# 01_Raspberry_Hat_4_Schematic.net
KiCad netlist of a schematic drawn in EAGLE
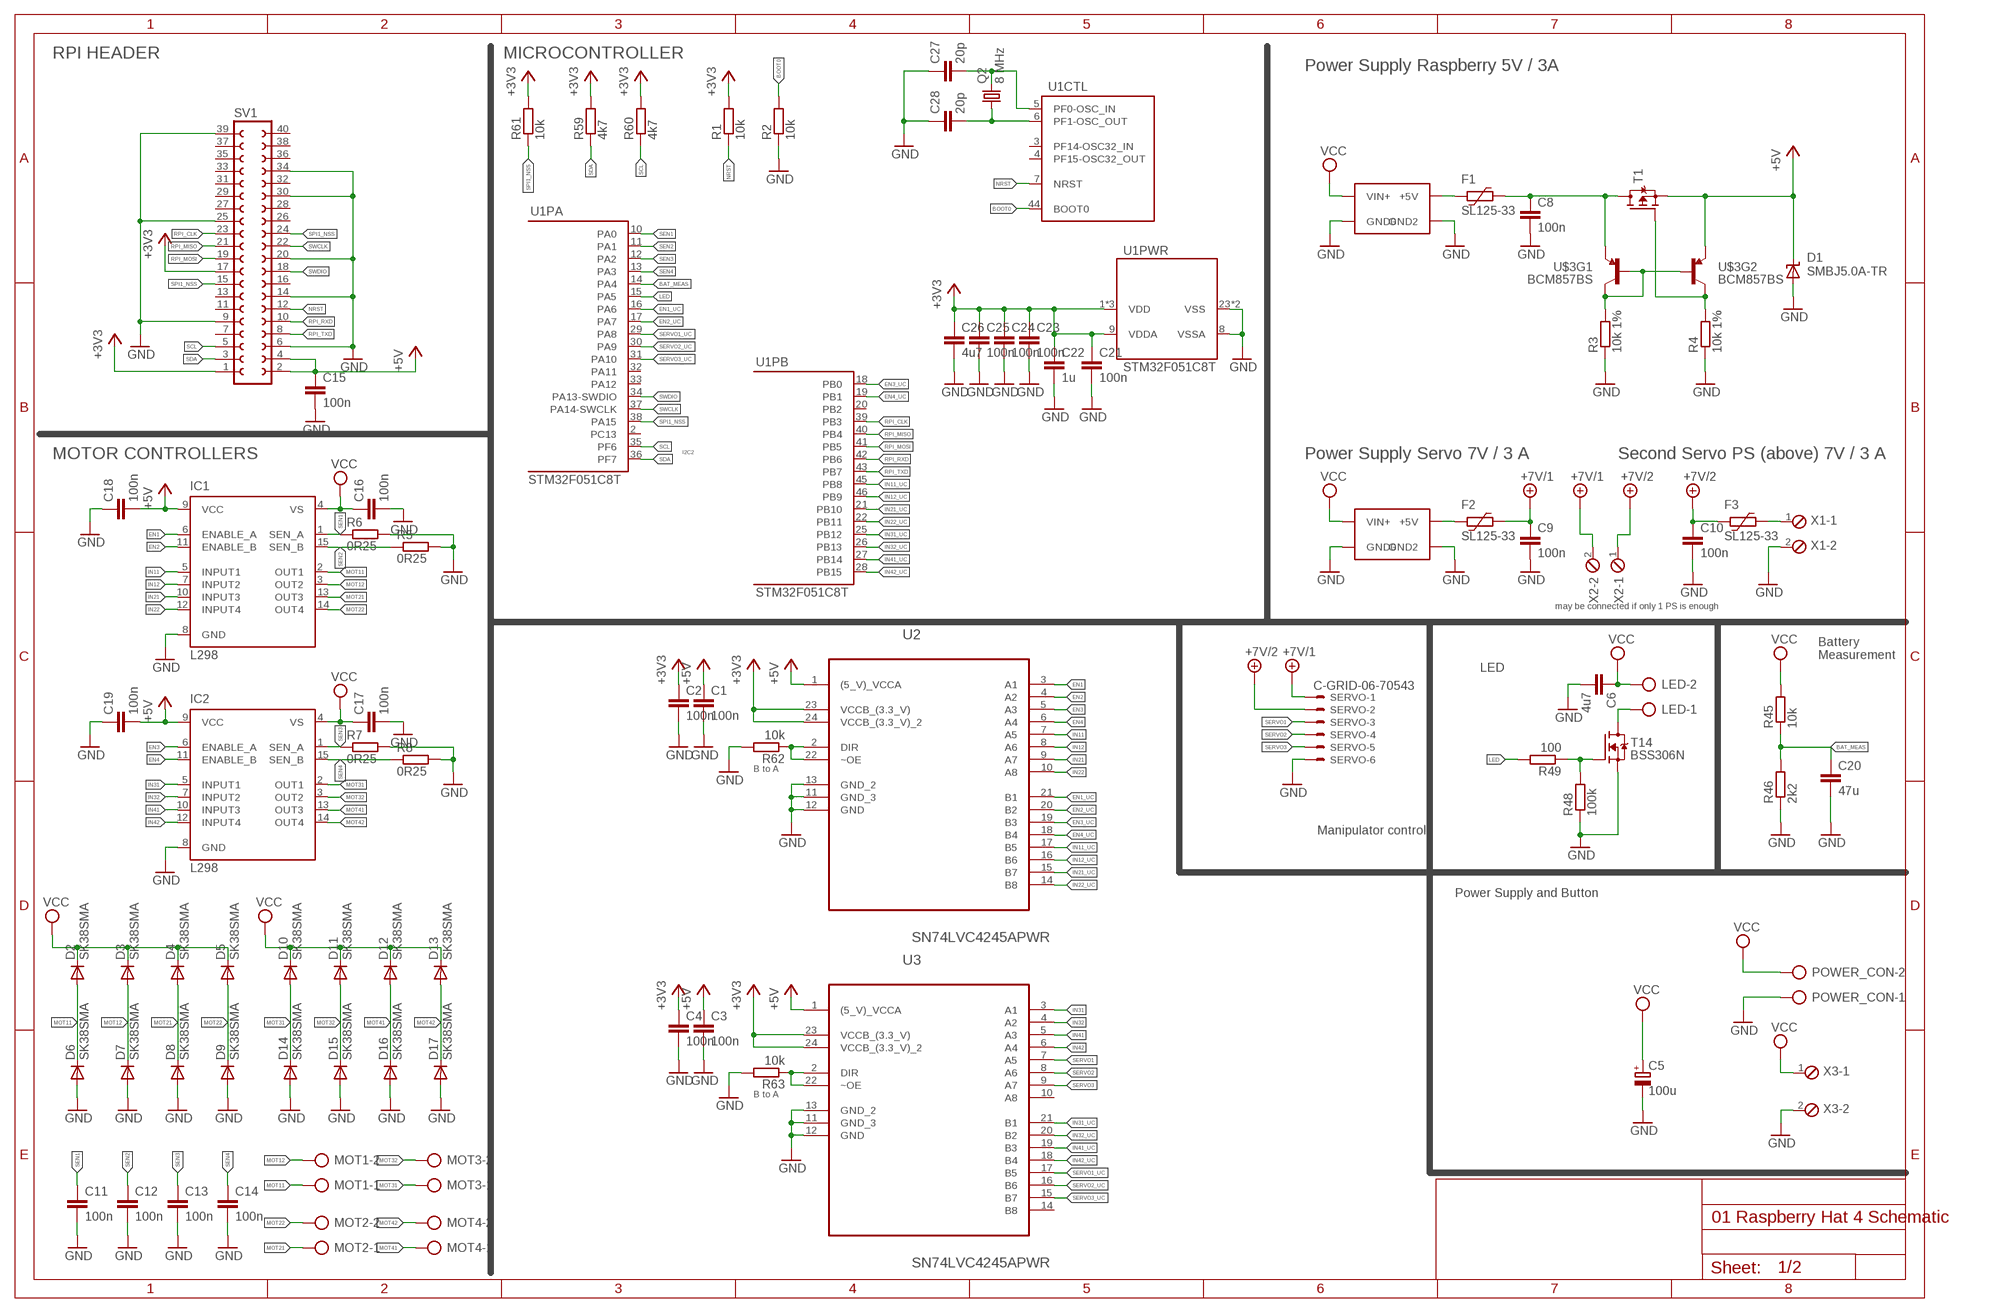
[diagram p0: schematic, sheet 1]
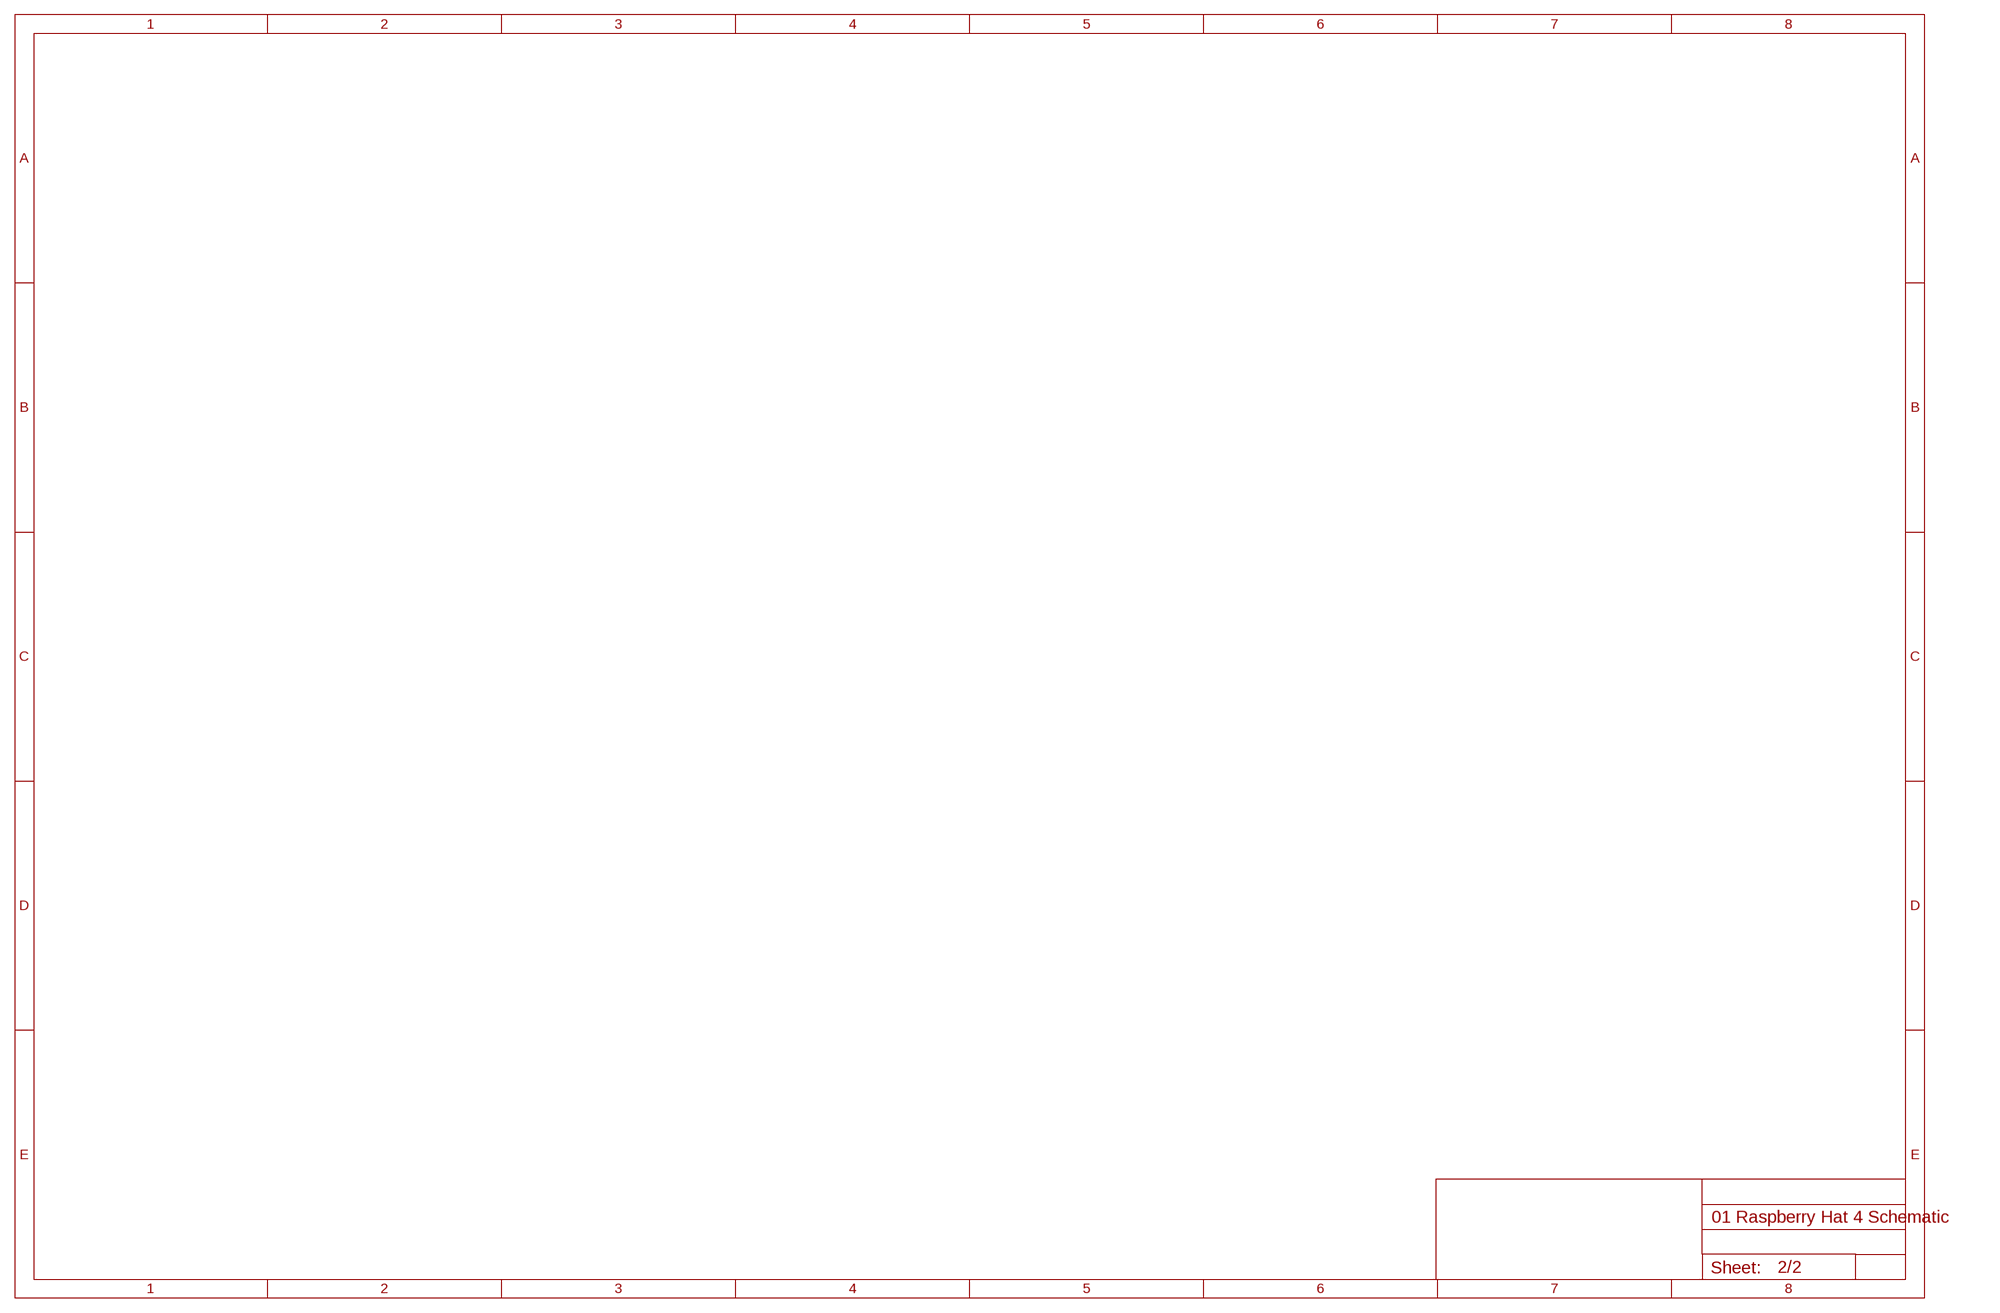
[diagram p1: schematic, sheet 2]

(export (version "E")
  (design (tool "Eeschema 10.0.6"))
  (components
    (comp (ref "C1")
      (value "100n")
      (footprint "eagle-import:C0805")
      (libsource (lib "eagle-import") (part "C-EUC0805"))
    )
    (comp (ref "C2")
      (value "100n")
      (footprint "eagle-import:C0805")
      (libsource (lib "eagle-import") (part "C-EUC0805"))
    )
    (comp (ref "C3")
      (value "100n")
      (footprint "eagle-import:C0805")
      (libsource (lib "eagle-import") (part "C-EUC0805"))
    )
    (comp (ref "C4")
      (value "100n")
      (footprint "eagle-import:C0805")
      (libsource (lib "eagle-import") (part "C-EUC0805"))
    )
    (comp (ref "C5")
      (value "100u")
      (footprint "eagle-import:153CLV-0807")
      (libsource (lib "eagle-import") (part "CPOL-EU153CLV-0807"))
    )
    (comp (ref "C6")
      (value "4u7")
      (footprint "eagle-import:C0805")
      (libsource (lib "eagle-import") (part "C-EUC0805"))
    )
    (comp (ref "C8")
      (value "100n")
      (footprint "eagle-import:C0805")
      (libsource (lib "eagle-import") (part "C-EUC0805"))
    )
    (comp (ref "C9")
      (value "100n")
      (footprint "eagle-import:C0805")
      (libsource (lib "eagle-import") (part "C-EUC0805"))
    )
    (comp (ref "C10")
      (value "100n")
      (footprint "eagle-import:C0805")
      (libsource (lib "eagle-import") (part "C-EUC0805"))
    )
    (comp (ref "C11")
      (value "100n")
      (footprint "eagle-import:C0805")
      (libsource (lib "eagle-import") (part "C-EUC0805"))
    )
    (comp (ref "C12")
      (value "100n")
      (footprint "eagle-import:C0805")
      (libsource (lib "eagle-import") (part "C-EUC0805"))
    )
    (comp (ref "C13")
      (value "100n")
      (footprint "eagle-import:C0805")
      (libsource (lib "eagle-import") (part "C-EUC0805"))
    )
    (comp (ref "C14")
      (value "100n")
      (footprint "eagle-import:C0805")
      (libsource (lib "eagle-import") (part "C-EUC0805"))
    )
    (comp (ref "C15")
      (value "100n")
      (footprint "eagle-import:C0805")
      (libsource (lib "eagle-import") (part "C-EUC0805"))
    )
    (comp (ref "C16")
      (value "100n")
      (footprint "eagle-import:C0805")
      (libsource (lib "eagle-import") (part "C-EUC0805"))
    )
    (comp (ref "C17")
      (value "100n")
      (footprint "eagle-import:C0805")
      (libsource (lib "eagle-import") (part "C-EUC0805"))
    )
    (comp (ref "C18")
      (value "100n")
      (footprint "eagle-import:C0805")
      (libsource (lib "eagle-import") (part "C-EUC0805"))
    )
    (comp (ref "C19")
      (value "100n")
      (footprint "eagle-import:C0805")
      (libsource (lib "eagle-import") (part "C-EUC0805"))
    )
    (comp (ref "C20")
      (value "47u")
      (footprint "eagle-import:C0805")
      (libsource (lib "eagle-import") (part "C-EUC0805"))
    )
    (comp (ref "C21")
      (value "100n")
      (footprint "eagle-import:C0805")
      (libsource (lib "eagle-import") (part "C-EUC0805"))
    )
    (comp (ref "C22")
      (value "1u")
      (footprint "eagle-import:C0805")
      (libsource (lib "eagle-import") (part "C-EUC0805"))
    )
    (comp (ref "C23")
      (value "100n")
      (footprint "eagle-import:C0805")
      (libsource (lib "eagle-import") (part "C-EUC0805"))
    )
    (comp (ref "C24")
      (value "100n")
      (footprint "eagle-import:C0805")
      (libsource (lib "eagle-import") (part "C-EUC0805"))
    )
    (comp (ref "C25")
      (value "100n")
      (footprint "eagle-import:C0805")
      (libsource (lib "eagle-import") (part "C-EUC0805"))
    )
    (comp (ref "C26")
      (value "4u7")
      (footprint "eagle-import:C0805")
      (libsource (lib "eagle-import") (part "C-EUC0805"))
    )
    (comp (ref "C27")
      (value "20p")
      (footprint "eagle-import:C0805")
      (libsource (lib "eagle-import") (part "C-EUC0805"))
    )
    (comp (ref "C28")
      (value "20p")
      (footprint "eagle-import:C0805")
      (libsource (lib "eagle-import") (part "C-EUC0805"))
    )
    (comp (ref "D1")
      (value "SMBJ5.0A-TR")
      (footprint "eagle-import:SMBJ")
      (libsource (lib "eagle-import") (part "SUPPRESSOR-SMBJ"))
    )
    (comp (ref "D2")
      (value "SK38SMA")
      (footprint "eagle-import:DO214AC")
      (libsource (lib "eagle-import") (part "DIODE-DO214AC"))
    )
    (comp (ref "D3")
      (value "SK38SMA")
      (footprint "eagle-import:DO214AC")
      (libsource (lib "eagle-import") (part "DIODE-DO214AC"))
    )
    (comp (ref "D4")
      (value "SK38SMA")
      (footprint "eagle-import:DO214AC")
      (libsource (lib "eagle-import") (part "DIODE-DO214AC"))
    )
    (comp (ref "D5")
      (value "SK38SMA")
      (footprint "eagle-import:DO214AC")
      (libsource (lib "eagle-import") (part "DIODE-DO214AC"))
    )
    (comp (ref "D6")
      (value "SK38SMA")
      (footprint "eagle-import:DO214AC")
      (libsource (lib "eagle-import") (part "DIODE-DO214AC"))
    )
    (comp (ref "D7")
      (value "SK38SMA")
      (footprint "eagle-import:DO214AC")
      (libsource (lib "eagle-import") (part "DIODE-DO214AC"))
    )
    (comp (ref "D8")
      (value "SK38SMA")
      (footprint "eagle-import:DO214AC")
      (libsource (lib "eagle-import") (part "DIODE-DO214AC"))
    )
    (comp (ref "D9")
      (value "SK38SMA")
      (footprint "eagle-import:DO214AC")
      (libsource (lib "eagle-import") (part "DIODE-DO214AC"))
    )
    (comp (ref "D10")
      (value "SK38SMA")
      (footprint "eagle-import:DO214AC")
      (libsource (lib "eagle-import") (part "DIODE-DO214AC"))
    )
    (comp (ref "D11")
      (value "SK38SMA")
      (footprint "eagle-import:DO214AC")
      (libsource (lib "eagle-import") (part "DIODE-DO214AC"))
    )
    (comp (ref "D12")
      (value "SK38SMA")
      (footprint "eagle-import:DO214AC")
      (libsource (lib "eagle-import") (part "DIODE-DO214AC"))
    )
    (comp (ref "D13")
      (value "SK38SMA")
      (footprint "eagle-import:DO214AC")
      (libsource (lib "eagle-import") (part "DIODE-DO214AC"))
    )
    (comp (ref "D14")
      (value "SK38SMA")
      (footprint "eagle-import:DO214AC")
      (libsource (lib "eagle-import") (part "DIODE-DO214AC"))
    )
    (comp (ref "D15")
      (value "SK38SMA")
      (footprint "eagle-import:DO214AC")
      (libsource (lib "eagle-import") (part "DIODE-DO214AC"))
    )
    (comp (ref "D16")
      (value "SK38SMA")
      (footprint "eagle-import:DO214AC")
      (libsource (lib "eagle-import") (part "DIODE-DO214AC"))
    )
    (comp (ref "D17")
      (value "SK38SMA")
      (footprint "eagle-import:DO214AC")
      (libsource (lib "eagle-import") (part "DIODE-DO214AC"))
    )
    (comp (ref "F1")
      (value "SL125-33")
      (footprint "eagle-import:2920L")
      (fields (field (name "MF") "Littelfuse") (field (name "MPN") "2920L050"))
      (libsource (lib "eagle-import") (part "?2920L050"))
    )
    (comp (ref "F2")
      (value "SL125-33")
      (footprint "eagle-import:2920L")
      (fields (field (name "MF") "Littelfuse") (field (name "MPN") "2920L050"))
      (libsource (lib "eagle-import") (part "?2920L050"))
    )
    (comp (ref "F3")
      (value "SL125-33")
      (footprint "eagle-import:2920L")
      (fields (field (name "MF") "Littelfuse") (field (name "MPN") "2920L050"))
      (libsource (lib "eagle-import") (part "?2920L050"))
    )
    (comp (ref "IC1")
      (value "L298")
      (footprint "eagle-import:MULTIWATT-15")
      (fields (field (name "MPN") "L298N"))
      (libsource (lib "eagle-import") (part "L298"))
    )
    (comp (ref "IC2")
      (value "L298")
      (footprint "eagle-import:MULTIWATT-15")
      (fields (field (name "MPN") "L298N"))
      (libsource (lib "eagle-import") (part "L298"))
    )
    (comp (ref "LED")
      (value "AK500/2")
      (footprint "eagle-import:AK500_2")
      (libsource (lib "eagle-import") (part "AK500/2"))
    )
    (comp (ref "MOT1")
      (value "AK500/2")
      (footprint "eagle-import:AK500_2")
      (libsource (lib "eagle-import") (part "AK500/2"))
    )
    (comp (ref "MOT2")
      (value "AK500/2")
      (footprint "eagle-import:AK500_2")
      (libsource (lib "eagle-import") (part "AK500/2"))
    )
    (comp (ref "MOT3")
      (value "AK500/2")
      (footprint "eagle-import:AK500_2")
      (libsource (lib "eagle-import") (part "AK500/2"))
    )
    (comp (ref "MOT4")
      (value "AK500/2")
      (footprint "eagle-import:AK500_2")
      (libsource (lib "eagle-import") (part "AK500/2"))
    )
    (comp (ref "POWER_CON")
      (value "AK500/2")
      (footprint "eagle-import:AK500_2")
      (libsource (lib "eagle-import") (part "AK500/2"))
    )
    (comp (ref "Q2")
      (value "8 MHz")
      (footprint "eagle-import:HC49UP")
      (libsource (lib "eagle-import") (part "CRYSTALHC49UP"))
    )
    (comp (ref "R1")
      (value "10k")
      (footprint "eagle-import:M0805")
      (libsource (lib "eagle-import") (part "resistor_R-EU_M0805"))
    )
    (comp (ref "R2")
      (value "10k")
      (footprint "eagle-import:M0805")
      (libsource (lib "eagle-import") (part "resistor_R-EU_M0805"))
    )
    (comp (ref "R3")
      (value "10k 1%")
      (footprint "eagle-import:M0805")
      (libsource (lib "eagle-import") (part "resistor_R-EU_M0805"))
    )
    (comp (ref "R4")
      (value "10k 1%")
      (footprint "eagle-import:M0805")
      (libsource (lib "eagle-import") (part "resistor_R-EU_M0805"))
    )
    (comp (ref "R5")
      (value "0R25")
      (footprint "eagle-import:R2512")
      (libsource (lib "eagle-import") (part "R-EU_R2512"))
    )
    (comp (ref "R6")
      (value "0R25")
      (footprint "eagle-import:R2512")
      (libsource (lib "eagle-import") (part "R-EU_R2512"))
    )
    (comp (ref "R7")
      (value "0R25")
      (footprint "eagle-import:R2512")
      (libsource (lib "eagle-import") (part "R-EU_R2512"))
    )
    (comp (ref "R8")
      (value "0R25")
      (footprint "eagle-import:R2512")
      (libsource (lib "eagle-import") (part "R-EU_R2512"))
    )
    (comp (ref "R45")
      (value "10k")
      (footprint "eagle-import:M0805")
      (libsource (lib "eagle-import") (part "resistor_R-EU_M0805"))
    )
    (comp (ref "R46")
      (value "2k2")
      (footprint "eagle-import:M0805")
      (libsource (lib "eagle-import") (part "resistor_R-EU_M0805"))
    )
    (comp (ref "R48")
      (value "100k")
      (footprint "eagle-import:M0805")
      (libsource (lib "eagle-import") (part "resistor_R-EU_M0805"))
    )
    (comp (ref "R49")
      (value "100")
      (footprint "eagle-import:M0805")
      (libsource (lib "eagle-import") (part "resistor_R-EU_M0805"))
    )
    (comp (ref "R59")
      (value "4k7")
      (footprint "eagle-import:M0805")
      (libsource (lib "eagle-import") (part "resistor_R-EU_M0805"))
    )
    (comp (ref "R60")
      (value "4k7")
      (footprint "eagle-import:M0805")
      (libsource (lib "eagle-import") (part "resistor_R-EU_M0805"))
    )
    (comp (ref "R61")
      (value "10k")
      (footprint "eagle-import:M0805")
      (libsource (lib "eagle-import") (part "resistor_R-EU_M0805"))
    )
    (comp (ref "R62")
      (value "10k")
      (footprint "eagle-import:M0805")
      (libsource (lib "eagle-import") (part "resistor_R-EU_M0805"))
    )
    (comp (ref "R63")
      (value "10k")
      (footprint "eagle-import:M0805")
      (libsource (lib "eagle-import") (part "resistor_R-EU_M0805"))
    )
    (comp (ref "SERVO")
      (value "C-GRID-06-70543")
      (footprint "eagle-import:70543-06")
      (fields
        (field (name "LINK") "http://www.tme.eu/pl/details/ncdw-06/zlacza-sygnalowe-raster-254mm/ninigi/")
      )
      (libsource (lib "eagle-import") (part "C-GRID-06-70543"))
    )
    (comp (ref "SV1")
      (value "FE20-2")
      (footprint "eagle-import:FE20-2")
      (libsource (lib "eagle-import") (part "FE20-2"))
    )
    (comp (ref "T1")
      (value "MOSFET-P-SOT23")
      (footprint "eagle-import:SOT23")
      (libsource (lib "eagle-import") (part "MOSFET-P-SOT23"))
    )
    (comp (ref "T14")
      (value "BSS306N")
      (footprint "eagle-import:SOT23")
      (libsource (lib "eagle-import") (part "MOSFET-N-SOT23"))
    )
    (comp (ref "U$2")
      (value "LM2596_CONVERTER")
      (footprint "eagle-import:LM2596_CONVERTER")
      (libsource (lib "eagle-import") (part "LM2596_CONVERTER"))
    )
    (comp (ref "U$3")
      (value "BCM857BS")
      (footprint "eagle-import:SOT363")
      (fields (field (name "LINK") "http://www.tme.eu/pl/details/bcm857bs/tranzystory-pnp-smd/nxp/"))
      (libsource (lib "eagle-import") (part "BCM857BS"))
    )
    (comp (ref "U$4")
      (value "LM2596_CONVERTER")
      (footprint "eagle-import:LM2596_CONVERTER")
      (libsource (lib "eagle-import") (part "LM2596_CONVERTER"))
    )
    (comp (ref "U1")
      (value "STM32F051C8T")
      (footprint "eagle-import:LQFP48")
      (libsource (lib "eagle-import") (part "STM32F051CT8"))
    )
    (comp (ref "U2")
      (value "SN74LVC4245APWR")
      (footprint "eagle-import:SOP65P640X120-24N")
      (libsource (lib "eagle-import") (part "SN74LVC4245APWR"))
    )
    (comp (ref "U3")
      (value "SN74LVC4245APWR")
      (footprint "eagle-import:SOP65P640X120-24N")
      (libsource (lib "eagle-import") (part "SN74LVC4245APWR"))
    )
    (comp (ref "X1")
      (value "MPT2")
      (footprint "eagle-import:2POL254")
      (libsource (lib "eagle-import") (part "MPT2"))
    )
    (comp (ref "X2")
      (value "MPT2")
      (footprint "eagle-import:2POL254")
      (libsource (lib "eagle-import") (part "MPT2"))
    )
    (comp (ref "X3")
      (value "MPT2")
      (footprint "eagle-import:2POL254")
      (libsource (lib "eagle-import") (part "MPT2"))
    )
  )
  (nets
    (net (code "1") (name "+3V3") (class "Default")
      (node (ref "C2") (pin "1") (pinfunction "1_1") (pintype "passive"))
      (node (ref "C21") (pin "1") (pinfunction "1_1") (pintype "passive"))
      (node (ref "C22") (pin "1") (pinfunction "1_1") (pintype "passive"))
      (node (ref "C23") (pin "1") (pinfunction "1_1") (pintype "passive"))
      (node (ref "C24") (pin "1") (pinfunction "1_1") (pintype "passive"))
      (node (ref "C25") (pin "1") (pinfunction "1_1") (pintype "passive"))
      (node (ref "C26") (pin "1") (pinfunction "1_1") (pintype "passive"))
      (node (ref "C4") (pin "1") (pinfunction "1_1") (pintype "passive"))
      (node (ref "R1") (pin "2") (pinfunction "2_2") (pintype "passive"))
      (node (ref "R59") (pin "2") (pinfunction "2_2") (pintype "passive"))
      (node (ref "R60") (pin "2") (pinfunction "2_2") (pintype "passive"))
      (node (ref "R61") (pin "2") (pinfunction "2_2") (pintype "passive"))
      (node (ref "SV1") (pin "1") (pinfunction "1_1") (pintype "passive"))
      (node (ref "SV1") (pin "17") (pinfunction "17_17") (pintype "passive"))
      (node (ref "U1") (pin "1") (pinfunction "VDD_1") (pintype "power_in"))
      (node (ref "U1") (pin "24") (pinfunction "VDD_24") (pintype "power_in"))
      (node (ref "U1") (pin "48") (pinfunction "VDD_48") (pintype "power_in"))
      (node (ref "U1") (pin "9") (pinfunction "VDDA_9") (pintype "power_in"))
      (node (ref "U2") (pin "23") (pinfunction "VCCB_(3.3_V)_23") (pintype "power_in"))
      (node (ref "U2") (pin "24") (pinfunction "VCCB_(3.3_V)_2_24") (pintype "power_in"))
      (node (ref "U3") (pin "23") (pinfunction "VCCB_(3.3_V)_23") (pintype "power_in"))
      (node (ref "U3") (pin "24") (pinfunction "VCCB_(3.3_V)_2_24") (pintype "power_in"))
    )
    (net (code "2") (name "+5V") (class "Default")
      (node (ref "C1") (pin "1") (pinfunction "1_1") (pintype "passive"))
      (node (ref "C15") (pin "1") (pinfunction "1_1") (pintype "passive"))
      (node (ref "C18") (pin "2") (pinfunction "2_2") (pintype "passive"))
      (node (ref "C19") (pin "2") (pinfunction "2_2") (pintype "passive"))
      (node (ref "C3") (pin "1") (pinfunction "1_1") (pintype "passive"))
      (node (ref "D1") (pin "C") (pinfunction "C_C") (pintype "passive"))
      (node (ref "IC1") (pin "9") (pinfunction "VCC_9") (pintype "power_in"))
      (node (ref "IC2") (pin "9") (pinfunction "VCC_9") (pintype "power_in"))
      (node (ref "SV1") (pin "2") (pinfunction "2_2") (pintype "passive"))
      (node (ref "SV1") (pin "4") (pinfunction "4_4") (pintype "passive"))
      (node (ref "T1") (pin "2") (pinfunction "S_2") (pintype "passive"))
      (node (ref "U$3") (pin "4") (pinfunction "E_4") (pintype "passive"))
      (node (ref "U2") (pin "1") (pinfunction "(5_V)_VCCA_1") (pintype "power_in"))
      (node (ref "U3") (pin "1") (pinfunction "(5_V)_VCCA_1") (pintype "power_in"))
    )
    (net (code "3") (name "+7V{slash}1") (class "Default")
      (node (ref "C9") (pin "1") (pinfunction "1_1") (pintype "passive"))
      (node (ref "F2") (pin "1") (pinfunction "1_1") (pintype "passive"))
      (node (ref "SERVO") (pin "1") (pinfunction "S_1") (pintype "passive"))
      (node (ref "X2") (pin "2") (pinfunction "1_2") (pintype "passive"))
    )
    (net (code "4") (name "+7V{slash}2") (class "Default")
      (node (ref "C10") (pin "1") (pinfunction "1_1") (pintype "passive"))
      (node (ref "F3") (pin "2") (pinfunction "2_2") (pintype "passive"))
      (node (ref "SERVO") (pin "2") (pinfunction "S_2") (pintype "passive"))
      (node (ref "X2") (pin "1") (pinfunction "1_1") (pintype "passive"))
    )
    (net (code "5") (name "BAT_MEAS") (class "Default")
      (node (ref "C20") (pin "1") (pinfunction "1_1") (pintype "passive"))
      (node (ref "R45") (pin "1") (pinfunction "1_1") (pintype "passive"))
      (node (ref "R46") (pin "2") (pinfunction "2_2") (pintype "passive"))
      (node (ref "U1") (pin "14") (pinfunction "PA4_14") (pintype "bidirectional"))
    )
    (net (code "6") (name "BOOT0") (class "Default")
      (node (ref "R2") (pin "2") (pinfunction "2_2") (pintype "passive"))
      (node (ref "U1") (pin "44") (pinfunction "BOOT0_44") (pintype "bidirectional"))
    )
    (net (code "7") (name "EN1") (class "Default")
      (node (ref "IC1") (pin "6") (pinfunction "ENABLE_A_6") (pintype "input"))
      (node (ref "U2") (pin "3") (pinfunction "A1_3") (pintype "output"))
    )
    (net (code "8") (name "EN1_UC") (class "Default")
      (node (ref "U1") (pin "16") (pinfunction "PA6_16") (pintype "bidirectional"))
      (node (ref "U2") (pin "21") (pinfunction "B1_21") (pintype "output"))
    )
    (net (code "9") (name "EN2") (class "Default")
      (node (ref "IC1") (pin "11") (pinfunction "ENABLE_B_11") (pintype "input"))
      (node (ref "U2") (pin "4") (pinfunction "A2_4") (pintype "output"))
    )
    (net (code "10") (name "EN2_UC") (class "Default")
      (node (ref "U1") (pin "17") (pinfunction "PA7_17") (pintype "bidirectional"))
      (node (ref "U2") (pin "20") (pinfunction "B2_20") (pintype "output"))
    )
    (net (code "11") (name "EN3") (class "Default")
      (node (ref "IC2") (pin "6") (pinfunction "ENABLE_A_6") (pintype "input"))
      (node (ref "U2") (pin "5") (pinfunction "A3_5") (pintype "output"))
    )
    (net (code "12") (name "EN3_UC") (class "Default")
      (node (ref "U1") (pin "18") (pinfunction "PB0_18") (pintype "bidirectional"))
      (node (ref "U2") (pin "19") (pinfunction "B3_19") (pintype "output"))
    )
    (net (code "13") (name "EN4") (class "Default")
      (node (ref "IC2") (pin "11") (pinfunction "ENABLE_B_11") (pintype "input"))
      (node (ref "U2") (pin "6") (pinfunction "A4_6") (pintype "output"))
    )
    (net (code "14") (name "EN4_UC") (class "Default")
      (node (ref "U1") (pin "19") (pinfunction "PB1_19") (pintype "bidirectional"))
      (node (ref "U2") (pin "18") (pinfunction "B4_18") (pintype "output"))
    )
    (net (code "15") (name "GND") (class "Default")
      (node (ref "C1") (pin "2") (pinfunction "2_2") (pintype "passive"))
      (node (ref "C10") (pin "2") (pinfunction "2_2") (pintype "passive"))
      (node (ref "C11") (pin "2") (pinfunction "2_2") (pintype "passive"))
      (node (ref "C12") (pin "2") (pinfunction "2_2") (pintype "passive"))
      (node (ref "C13") (pin "2") (pinfunction "2_2") (pintype "passive"))
      (node (ref "C14") (pin "2") (pinfunction "2_2") (pintype "passive"))
      (node (ref "C15") (pin "2") (pinfunction "2_2") (pintype "passive"))
      (node (ref "C16") (pin "2") (pinfunction "2_2") (pintype "passive"))
      (node (ref "C17") (pin "2") (pinfunction "2_2") (pintype "passive"))
      (node (ref "C18") (pin "1") (pinfunction "1_1") (pintype "passive"))
      (node (ref "C19") (pin "1") (pinfunction "1_1") (pintype "passive"))
      (node (ref "C2") (pin "2") (pinfunction "2_2") (pintype "passive"))
      (node (ref "C20") (pin "2") (pinfunction "2_2") (pintype "passive"))
      (node (ref "C21") (pin "2") (pinfunction "2_2") (pintype "passive"))
      (node (ref "C22") (pin "2") (pinfunction "2_2") (pintype "passive"))
      (node (ref "C23") (pin "2") (pinfunction "2_2") (pintype "passive"))
      (node (ref "C24") (pin "2") (pinfunction "2_2") (pintype "passive"))
      (node (ref "C25") (pin "2") (pinfunction "2_2") (pintype "passive"))
      (node (ref "C26") (pin "2") (pinfunction "2_2") (pintype "passive"))
      (node (ref "C27") (pin "1") (pinfunction "1_1") (pintype "passive"))
      (node (ref "C28") (pin "1") (pinfunction "1_1") (pintype "passive"))
      (node (ref "C3") (pin "2") (pinfunction "2_2") (pintype "passive"))
      (node (ref "C4") (pin "2") (pinfunction "2_2") (pintype "passive"))
      (node (ref "C5") (pin "-") (pinfunction "-_-") (pintype "passive"))
      (node (ref "C6") (pin "2") (pinfunction "2_2") (pintype "passive"))
      (node (ref "C8") (pin "2") (pinfunction "2_2") (pintype "passive"))
      (node (ref "C9") (pin "2") (pinfunction "2_2") (pintype "passive"))
      (node (ref "D1") (pin "A") (pinfunction "A_A") (pintype "passive"))
      (node (ref "D14") (pin "A") (pinfunction "A_A") (pintype "passive"))
      (node (ref "D15") (pin "A") (pinfunction "A_A") (pintype "passive"))
      (node (ref "D16") (pin "A") (pinfunction "A_A") (pintype "passive"))
      (node (ref "D17") (pin "A") (pinfunction "A_A") (pintype "passive"))
      (node (ref "D6") (pin "A") (pinfunction "A_A") (pintype "passive"))
      (node (ref "D7") (pin "A") (pinfunction "A_A") (pintype "passive"))
      (node (ref "D8") (pin "A") (pinfunction "A_A") (pintype "passive"))
      (node (ref "D9") (pin "A") (pinfunction "A_A") (pintype "passive"))
      (node (ref "IC1") (pin "8") (pinfunction "GND_8") (pintype "power_in"))
      (node (ref "IC2") (pin "8") (pinfunction "GND_8") (pintype "power_in"))
      (node (ref "POWER_CON") (pin "1") (pinfunction "KL_1") (pintype "passive"))
      (node (ref "R2") (pin "1") (pinfunction "1_1") (pintype "passive"))
      (node (ref "R3") (pin "1") (pinfunction "1_1") (pintype "passive"))
      (node (ref "R4") (pin "1") (pinfunction "1_1") (pintype "passive"))
      (node (ref "R46") (pin "1") (pinfunction "1_1") (pintype "passive"))
      (node (ref "R48") (pin "1") (pinfunction "1_1") (pintype "passive"))
      (node (ref "R5") (pin "2") (pinfunction "2_2") (pintype "passive"))
      (node (ref "R6") (pin "2") (pinfunction "2_2") (pintype "passive"))
      (node (ref "R62") (pin "2") (pinfunction "2_2") (pintype "passive"))
      (node (ref "R63") (pin "2") (pinfunction "2_2") (pintype "passive"))
      (node (ref "R7") (pin "2") (pinfunction "2_2") (pintype "passive"))
      (node (ref "R8") (pin "2") (pinfunction "2_2") (pintype "passive"))
      (node (ref "SERVO") (pin "6") (pinfunction "S_6") (pintype "passive"))
      (node (ref "SV1") (pin "14") (pinfunction "14_14") (pintype "passive"))
      (node (ref "SV1") (pin "20") (pinfunction "20_20") (pintype "passive"))
      (node (ref "SV1") (pin "25") (pinfunction "25_25") (pintype "passive"))
      (node (ref "SV1") (pin "30") (pinfunction "30_30") (pintype "passive"))
      (node (ref "SV1") (pin "34") (pinfunction "34_34") (pintype "passive"))
      (node (ref "SV1") (pin "39") (pinfunction "39_39") (pintype "passive"))
      (node (ref "SV1") (pin "6") (pinfunction "6_6") (pintype "passive"))
      (node (ref "SV1") (pin "9") (pinfunction "9_9") (pintype "passive"))
      (node (ref "T14") (pin "2") (pinfunction "S_2") (pintype "passive"))
      (node (ref "U$2") (pin "GND") (pinfunction "GND0_GND") (pintype "input"))
      (node (ref "U$2") (pin "GND1") (pinfunction "GND2_GND1") (pintype "output"))
      (node (ref "U$4") (pin "GND") (pinfunction "GND0_GND") (pintype "input"))
      (node (ref "U$4") (pin "GND1") (pinfunction "GND2_GND1") (pintype "output"))
      (node (ref "U1") (pin "23") (pinfunction "VSS_23") (pintype "power_in"))
      (node (ref "U1") (pin "47") (pinfunction "VSS_47") (pintype "power_in"))
      (node (ref "U1") (pin "8") (pinfunction "VSSA_8") (pintype "power_in"))
      (node (ref "U2") (pin "11") (pinfunction "GND_3_11") (pintype "passive"))
      (node (ref "U2") (pin "12") (pinfunction "GND_12") (pintype "passive"))
      (node (ref "U2") (pin "13") (pinfunction "GND_2_13") (pintype "passive"))
      (node (ref "U3") (pin "11") (pinfunction "GND_3_11") (pintype "passive"))
      (node (ref "U3") (pin "12") (pinfunction "GND_12") (pintype "passive"))
      (node (ref "U3") (pin "13") (pinfunction "GND_2_13") (pintype "passive"))
      (node (ref "X1") (pin "2") (pinfunction "1_2") (pintype "passive"))
      (node (ref "X3") (pin "2") (pinfunction "1_2") (pintype "passive"))
    )
    (net (code "16") (name "IN11") (class "Default")
      (node (ref "IC1") (pin "5") (pinfunction "INPUT1_5") (pintype "input"))
      (node (ref "U2") (pin "7") (pinfunction "A5_7") (pintype "output"))
    )
    (net (code "17") (name "IN11_UC") (class "Default")
      (node (ref "U1") (pin "45") (pinfunction "PB8_45") (pintype "bidirectional"))
      (node (ref "U2") (pin "17") (pinfunction "B5_17") (pintype "output"))
    )
    (net (code "18") (name "IN12") (class "Default")
      (node (ref "IC1") (pin "7") (pinfunction "INPUT2_7") (pintype "input"))
      (node (ref "U2") (pin "8") (pinfunction "A6_8") (pintype "output"))
    )
    (net (code "19") (name "IN12_UC") (class "Default")
      (node (ref "U1") (pin "46") (pinfunction "PB9_46") (pintype "bidirectional"))
      (node (ref "U2") (pin "16") (pinfunction "B6_16") (pintype "output"))
    )
    (net (code "20") (name "IN21") (class "Default")
      (node (ref "IC1") (pin "10") (pinfunction "INPUT3_10") (pintype "input"))
      (node (ref "U2") (pin "9") (pinfunction "A7_9") (pintype "output"))
    )
    (net (code "21") (name "IN21_UC") (class "Default")
      (node (ref "U1") (pin "21") (pinfunction "PB10_21") (pintype "bidirectional"))
      (node (ref "U2") (pin "15") (pinfunction "B7_15") (pintype "output"))
    )
    (net (code "22") (name "IN22") (class "Default")
      (node (ref "IC1") (pin "12") (pinfunction "INPUT4_12") (pintype "input"))
      (node (ref "U2") (pin "10") (pinfunction "A8_10") (pintype "output"))
    )
    (net (code "23") (name "IN22_UC") (class "Default")
      (node (ref "U1") (pin "22") (pinfunction "PB11_22") (pintype "bidirectional"))
      (node (ref "U2") (pin "14") (pinfunction "B8_14") (pintype "output"))
    )
    (net (code "24") (name "IN31") (class "Default")
      (node (ref "IC2") (pin "5") (pinfunction "INPUT1_5") (pintype "input"))
      (node (ref "U3") (pin "3") (pinfunction "A1_3") (pintype "output"))
    )
    (net (code "25") (name "IN31_UC") (class "Default")
      (node (ref "U1") (pin "25") (pinfunction "PB12_25") (pintype "bidirectional"))
      (node (ref "U3") (pin "21") (pinfunction "B1_21") (pintype "output"))
    )
    (net (code "26") (name "IN32") (class "Default")
      (node (ref "IC2") (pin "7") (pinfunction "INPUT2_7") (pintype "input"))
      (node (ref "U3") (pin "4") (pinfunction "A2_4") (pintype "output"))
    )
    (net (code "27") (name "IN32_UC") (class "Default")
      (node (ref "U1") (pin "26") (pinfunction "PB13_26") (pintype "bidirectional"))
      (node (ref "U3") (pin "20") (pinfunction "B2_20") (pintype "output"))
    )
    (net (code "28") (name "IN41") (class "Default")
      (node (ref "IC2") (pin "10") (pinfunction "INPUT3_10") (pintype "input"))
      (node (ref "U3") (pin "5") (pinfunction "A3_5") (pintype "output"))
    )
    (net (code "29") (name "IN41_UC") (class "Default")
      (node (ref "U1") (pin "27") (pinfunction "PB14_27") (pintype "bidirectional"))
      (node (ref "U3") (pin "19") (pinfunction "B3_19") (pintype "output"))
    )
    (net (code "30") (name "IN42") (class "Default")
      (node (ref "IC2") (pin "12") (pinfunction "INPUT4_12") (pintype "input"))
      (node (ref "U3") (pin "6") (pinfunction "A4_6") (pintype "output"))
    )
    (net (code "31") (name "IN42_UC") (class "Default")
      (node (ref "U1") (pin "28") (pinfunction "PB15_28") (pintype "bidirectional"))
      (node (ref "U3") (pin "18") (pinfunction "B4_18") (pintype "output"))
    )
    (net (code "32") (name "LED") (class "Default")
      (node (ref "R49") (pin "2") (pinfunction "2_2") (pintype "passive"))
      (node (ref "U1") (pin "15") (pinfunction "PA5_15") (pintype "bidirectional"))
    )
    (net (code "33") (name "MOT11") (class "Default")
      (node (ref "D2") (pin "A") (pinfunction "A_A") (pintype "passive"))
      (node (ref "D6") (pin "C") (pinfunction "C_C") (pintype "passive"))
      (node (ref "IC1") (pin "2") (pinfunction "OUT1_2") (pintype "output"))
      (node (ref "MOT1") (pin "1") (pinfunction "KL_1") (pintype "passive"))
    )
    (net (code "34") (name "MOT12") (class "Default")
      (node (ref "D3") (pin "A") (pinfunction "A_A") (pintype "passive"))
      (node (ref "D7") (pin "C") (pinfunction "C_C") (pintype "passive"))
      (node (ref "IC1") (pin "3") (pinfunction "OUT2_3") (pintype "output"))
      (node (ref "MOT1") (pin "2") (pinfunction "KL_2") (pintype "passive"))
    )
    (net (code "35") (name "MOT21") (class "Default")
      (node (ref "D4") (pin "A") (pinfunction "A_A") (pintype "passive"))
      (node (ref "D8") (pin "C") (pinfunction "C_C") (pintype "passive"))
      (node (ref "IC1") (pin "13") (pinfunction "OUT3_13") (pintype "output"))
      (node (ref "MOT2") (pin "1") (pinfunction "KL_1") (pintype "passive"))
    )
    (net (code "36") (name "MOT22") (class "Default")
      (node (ref "D5") (pin "A") (pinfunction "A_A") (pintype "passive"))
      (node (ref "D9") (pin "C") (pinfunction "C_C") (pintype "passive"))
      (node (ref "IC1") (pin "14") (pinfunction "OUT4_14") (pintype "output"))
      (node (ref "MOT2") (pin "2") (pinfunction "KL_2") (pintype "passive"))
    )
    (net (code "37") (name "MOT31") (class "Default")
      (node (ref "D10") (pin "A") (pinfunction "A_A") (pintype "passive"))
      (node (ref "D14") (pin "C") (pinfunction "C_C") (pintype "passive"))
      (node (ref "IC2") (pin "2") (pinfunction "OUT1_2") (pintype "output"))
      (node (ref "MOT3") (pin "1") (pinfunction "KL_1") (pintype "passive"))
    )
    (net (code "38") (name "MOT32") (class "Default")
      (node (ref "D11") (pin "A") (pinfunction "A_A") (pintype "passive"))
      (node (ref "D15") (pin "C") (pinfunction "C_C") (pintype "passive"))
      (node (ref "IC2") (pin "3") (pinfunction "OUT2_3") (pintype "output"))
      (node (ref "MOT3") (pin "2") (pinfunction "KL_2") (pintype "passive"))
    )
    (net (code "39") (name "MOT41") (class "Default")
      (node (ref "D12") (pin "A") (pinfunction "A_A") (pintype "passive"))
      (node (ref "D16") (pin "C") (pinfunction "C_C") (pintype "passive"))
      (node (ref "IC2") (pin "13") (pinfunction "OUT3_13") (pintype "output"))
      (node (ref "MOT4") (pin "1") (pinfunction "KL_1") (pintype "passive"))
    )
    (net (code "40") (name "MOT42") (class "Default")
      (node (ref "D13") (pin "A") (pinfunction "A_A") (pintype "passive"))
      (node (ref "D17") (pin "C") (pinfunction "C_C") (pintype "passive"))
      (node (ref "IC2") (pin "14") (pinfunction "OUT4_14") (pintype "output"))
      (node (ref "MOT4") (pin "2") (pinfunction "KL_2") (pintype "passive"))
    )
    (net (code "41") (name "NRST") (class "Default")
      (node (ref "R1") (pin "1") (pinfunction "1_1") (pintype "passive"))
      (node (ref "SV1") (pin "12") (pinfunction "12_12") (pintype "passive"))
      (node (ref "U1") (pin "7") (pinfunction "NRST_7") (pintype "bidirectional"))
    )
    (net (code "42") (name "Net-(F1-Pad2)") (class "Default")
      (node (ref "F1") (pin "2") (pinfunction "2_2") (pintype "passive"))
      (node (ref "U$2") (pin "+5V") (pinfunction "+5V_+5V") (pintype "output"))
    )
    (net (code "43") (name "Net-(F2-Pad2)") (class "Default")
      (node (ref "F2") (pin "2") (pinfunction "2_2") (pintype "passive"))
      (node (ref "U$4") (pin "+5V") (pinfunction "+5V_+5V") (pintype "output"))
    )
    (net (code "44") (name "Net-(F3-Pad1)") (class "Default")
      (node (ref "F3") (pin "1") (pinfunction "1_1") (pintype "passive"))
      (node (ref "X1") (pin "1") (pinfunction "1_1") (pintype "passive"))
    )
    (net (code "45") (name "Net-(LEDA-KL)") (class "Default")
      (node (ref "LED") (pin "1") (pinfunction "KL_1") (pintype "passive"))
      (node (ref "T14") (pin "3") (pinfunction "D_3") (pintype "passive"))
    )
    (net (code "46") (name "Net-(T1-D)") (class "Default")
      (node (ref "C8") (pin "1") (pinfunction "1_1") (pintype "passive"))
      (node (ref "F1") (pin "1") (pinfunction "1_1") (pintype "passive"))
      (node (ref "T1") (pin "3") (pinfunction "D_3") (pintype "passive"))
      (node (ref "U$3") (pin "1") (pinfunction "E_1") (pintype "passive"))
    )
    (net (code "47") (name "Net-(T1-G)") (class "Default")
      (node (ref "R4") (pin "2") (pinfunction "2_2") (pintype "passive"))
      (node (ref "T1") (pin "1") (pinfunction "G_1") (pintype "passive"))
      (node (ref "U$3") (pin "3") (pinfunction "C_3") (pintype "passive"))
    )
    (net (code "48") (name "Net-(T14-G)") (class "Default")
      (node (ref "R48") (pin "2") (pinfunction "2_2") (pintype "passive"))
      (node (ref "R49") (pin "1") (pinfunction "1_1") (pintype "passive"))
      (node (ref "T14") (pin "1") (pinfunction "G_1") (pintype "passive"))
    )
    (net (code "49") (name "Net-(U$3A-B)") (class "Default")
      (node (ref "R3") (pin "2") (pinfunction "2_2") (pintype "passive"))
      (node (ref "U$3") (pin "2") (pinfunction "B_2") (pintype "passive"))
      (node (ref "U$3") (pin "5") (pinfunction "B_5") (pintype "passive"))
      (node (ref "U$3") (pin "6") (pinfunction "C_6") (pintype "passive"))
    )
    (net (code "50") (name "Net-(U1A-PF0-OSC_IN)") (class "Default")
      (node (ref "C27") (pin "2") (pinfunction "2_2") (pintype "passive"))
      (node (ref "Q2") (pin "2") (pinfunction "2_2") (pintype "passive"))
      (node (ref "U1") (pin "5") (pinfunction "PF0-OSC_IN_5") (pintype "bidirectional"))
    )
    (net (code "51") (name "Net-(U1A-PF1-OSC_OUT)") (class "Default")
      (node (ref "C28") (pin "2") (pinfunction "2_2") (pintype "passive"))
      (node (ref "Q2") (pin "1") (pinfunction "1_1") (pintype "passive"))
      (node (ref "U1") (pin "6") (pinfunction "PF1-OSC_OUT_6") (pintype "bidirectional"))
    )
    (net (code "52") (name "Net-(U2-DIR)") (class "Default")
      (node (ref "R62") (pin "1") (pinfunction "1_1") (pintype "passive"))
      (node (ref "U2") (pin "2") (pinfunction "DIR_2") (pintype "input"))
      (node (ref "U2") (pin "22") (pinfunction "~{OE}_22") (pintype "input"))
    )
    (net (code "53") (name "Net-(U3-DIR)") (class "Default")
      (node (ref "R63") (pin "1") (pinfunction "1_1") (pintype "passive"))
      (node (ref "U3") (pin "2") (pinfunction "DIR_2") (pintype "input"))
      (node (ref "U3") (pin "22") (pinfunction "~{OE}_22") (pintype "input"))
    )
    (net (code "54") (name "RPI_CLK") (class "Default")
      (node (ref "SV1") (pin "23") (pinfunction "23_23") (pintype "passive"))
      (node (ref "U1") (pin "39") (pinfunction "PB3_39") (pintype "bidirectional"))
    )
    (net (code "55") (name "RPI_MISO") (class "Default")
      (node (ref "SV1") (pin "21") (pinfunction "21_21") (pintype "passive"))
      (node (ref "U1") (pin "40") (pinfunction "PB4_40") (pintype "bidirectional"))
    )
    (net (code "56") (name "RPI_MOSI") (class "Default")
      (node (ref "SV1") (pin "19") (pinfunction "19_19") (pintype "passive"))
      (node (ref "U1") (pin "41") (pinfunction "PB5_41") (pintype "bidirectional"))
    )
    (net (code "57") (name "RPI_RXD") (class "Default")
      (node (ref "SV1") (pin "10") (pinfunction "10_10") (pintype "passive"))
      (node (ref "U1") (pin "42") (pinfunction "PB6_42") (pintype "bidirectional"))
    )
    (net (code "58") (name "RPI_TXD") (class "Default")
      (node (ref "SV1") (pin "8") (pinfunction "8_8") (pintype "passive"))
      (node (ref "U1") (pin "43") (pinfunction "PB7_43") (pintype "bidirectional"))
    )
    (net (code "59") (name "SCL") (class "Default")
      (node (ref "R60") (pin "1") (pinfunction "1_1") (pintype "passive"))
      (node (ref "SV1") (pin "5") (pinfunction "5_5") (pintype "passive"))
      (node (ref "U1") (pin "35") (pinfunction "PF6_35") (pintype "bidirectional"))
    )
    (net (code "60") (name "SDA") (class "Default")
      (node (ref "R59") (pin "1") (pinfunction "1_1") (pintype "passive"))
      (node (ref "SV1") (pin "3") (pinfunction "3_3") (pintype "passive"))
      (node (ref "U1") (pin "36") (pinfunction "PF7_36") (pintype "bidirectional"))
    )
    (net (code "61") (name "SEN1") (class "Default")
      (node (ref "C11") (pin "1") (pinfunction "1_1") (pintype "passive"))
      (node (ref "IC1") (pin "1") (pinfunction "SEN_A_1") (pintype "input"))
      (node (ref "R6") (pin "1") (pinfunction "1_1") (pintype "passive"))
      (node (ref "U1") (pin "10") (pinfunction "PA0_10") (pintype "bidirectional"))
    )
    (net (code "62") (name "SEN2") (class "Default")
      (node (ref "C12") (pin "1") (pinfunction "1_1") (pintype "passive"))
      (node (ref "IC1") (pin "15") (pinfunction "SEN_B_15") (pintype "input"))
      (node (ref "R5") (pin "1") (pinfunction "1_1") (pintype "passive"))
      (node (ref "U1") (pin "11") (pinfunction "PA1_11") (pintype "bidirectional"))
    )
    (net (code "63") (name "SEN3") (class "Default")
      (node (ref "C13") (pin "1") (pinfunction "1_1") (pintype "passive"))
      (node (ref "IC2") (pin "1") (pinfunction "SEN_A_1") (pintype "input"))
      (node (ref "R7") (pin "1") (pinfunction "1_1") (pintype "passive"))
      (node (ref "U1") (pin "12") (pinfunction "PA2_12") (pintype "bidirectional"))
    )
    (net (code "64") (name "SEN4") (class "Default")
      (node (ref "C14") (pin "1") (pinfunction "1_1") (pintype "passive"))
      (node (ref "IC2") (pin "15") (pinfunction "SEN_B_15") (pintype "input"))
      (node (ref "R8") (pin "1") (pinfunction "1_1") (pintype "passive"))
      (node (ref "U1") (pin "13") (pinfunction "PA3_13") (pintype "bidirectional"))
    )
    (net (code "65") (name "SERVO1") (class "Default")
      (node (ref "SERVO") (pin "3") (pinfunction "S_3") (pintype "passive"))
      (node (ref "U3") (pin "7") (pinfunction "A5_7") (pintype "output"))
    )
    (net (code "66") (name "SERVO1_UC") (class "Default")
      (node (ref "U1") (pin "29") (pinfunction "PA8_29") (pintype "bidirectional"))
      (node (ref "U3") (pin "17") (pinfunction "B5_17") (pintype "output"))
    )
    (net (code "67") (name "SERVO2") (class "Default")
      (node (ref "SERVO") (pin "4") (pinfunction "S_4") (pintype "passive"))
      (node (ref "U3") (pin "8") (pinfunction "A6_8") (pintype "output"))
    )
    (net (code "68") (name "SERVO2_UC") (class "Default")
      (node (ref "U1") (pin "30") (pinfunction "PA9_30") (pintype "bidirectional"))
      (node (ref "U3") (pin "16") (pinfunction "B6_16") (pintype "output"))
    )
    (net (code "69") (name "SERVO3") (class "Default")
      (node (ref "SERVO") (pin "5") (pinfunction "S_5") (pintype "passive"))
      (node (ref "U3") (pin "9") (pinfunction "A7_9") (pintype "output"))
    )
    (net (code "70") (name "SERVO3_UC") (class "Default")
      (node (ref "U1") (pin "31") (pinfunction "PA10_31") (pintype "bidirectional"))
      (node (ref "U3") (pin "15") (pinfunction "B7_15") (pintype "output"))
    )
    (net (code "71") (name "SPI1_NSS") (class "Default")
      (node (ref "R61") (pin "1") (pinfunction "1_1") (pintype "passive"))
      (node (ref "SV1") (pin "15") (pinfunction "15_15") (pintype "passive"))
      (node (ref "SV1") (pin "24") (pinfunction "24_24") (pintype "passive"))
      (node (ref "U1") (pin "38") (pinfunction "PA15_38") (pintype "bidirectional"))
    )
    (net (code "72") (name "SWCLK") (class "Default")
      (node (ref "SV1") (pin "22") (pinfunction "22_22") (pintype "passive"))
      (node (ref "U1") (pin "37") (pinfunction "PA14-SWCLK_37") (pintype "bidirectional"))
    )
    (net (code "73") (name "SWDIO") (class "Default")
      (node (ref "SV1") (pin "18") (pinfunction "18_18") (pintype "passive"))
      (node (ref "U1") (pin "34") (pinfunction "PA13-SWDIO_34") (pintype "bidirectional"))
    )
    (net (code "74") (name "VCC") (class "Default")
      (node (ref "C16") (pin "1") (pinfunction "1_1") (pintype "passive"))
      (node (ref "C17") (pin "1") (pinfunction "1_1") (pintype "passive"))
      (node (ref "C5") (pin "+") (pinfunction "+_+") (pintype "passive"))
      (node (ref "C6") (pin "1") (pinfunction "1_1") (pintype "passive"))
      (node (ref "D10") (pin "C") (pinfunction "C_C") (pintype "passive"))
      (node (ref "D11") (pin "C") (pinfunction "C_C") (pintype "passive"))
      (node (ref "D12") (pin "C") (pinfunction "C_C") (pintype "passive"))
      (node (ref "D13") (pin "C") (pinfunction "C_C") (pintype "passive"))
      (node (ref "D2") (pin "C") (pinfunction "C_C") (pintype "passive"))
      (node (ref "D3") (pin "C") (pinfunction "C_C") (pintype "passive"))
      (node (ref "D4") (pin "C") (pinfunction "C_C") (pintype "passive"))
      (node (ref "D5") (pin "C") (pinfunction "C_C") (pintype "passive"))
      (node (ref "IC1") (pin "4") (pinfunction "VS_4") (pintype "power_in"))
      (node (ref "IC2") (pin "4") (pinfunction "VS_4") (pintype "power_in"))
      (node (ref "LED") (pin "2") (pinfunction "KL_2") (pintype "passive"))
      (node (ref "POWER_CON") (pin "2") (pinfunction "KL_2") (pintype "passive"))
      (node (ref "R45") (pin "2") (pinfunction "2_2") (pintype "passive"))
      (node (ref "U$2") (pin "IN+") (pinfunction "VIN+_IN+") (pintype "input"))
      (node (ref "U$4") (pin "IN+") (pinfunction "VIN+_IN+") (pintype "input"))
      (node (ref "X3") (pin "1") (pinfunction "1_1") (pintype "passive"))
    )
    (net (code "75") (name "unconnected-(SV1-Pad7)") (class "Default")
      (node (ref "SV1") (pin "7") (pinfunction "7_7") (pintype "passive"))
    )
    (net (code "76") (name "unconnected-(SV1-Pad11)") (class "Default")
      (node (ref "SV1") (pin "11") (pinfunction "11_11") (pintype "passive"))
    )
    (net (code "77") (name "unconnected-(SV1-Pad13)") (class "Default")
      (node (ref "SV1") (pin "13") (pinfunction "13_13") (pintype "passive"))
    )
    (net (code "78") (name "unconnected-(SV1-Pad16)") (class "Default")
      (node (ref "SV1") (pin "16") (pinfunction "16_16") (pintype "passive"))
    )
    (net (code "79") (name "unconnected-(SV1-Pad26)") (class "Default")
      (node (ref "SV1") (pin "26") (pinfunction "26_26") (pintype "passive"))
    )
    (net (code "80") (name "unconnected-(SV1-Pad27)") (class "Default")
      (node (ref "SV1") (pin "27") (pinfunction "27_27") (pintype "passive"))
    )
    (net (code "81") (name "unconnected-(SV1-Pad28)") (class "Default")
      (node (ref "SV1") (pin "28") (pinfunction "28_28") (pintype "passive"))
    )
    (net (code "82") (name "unconnected-(SV1-Pad29)") (class "Default")
      (node (ref "SV1") (pin "29") (pinfunction "29_29") (pintype "passive"))
    )
    (net (code "83") (name "unconnected-(SV1-Pad31)") (class "Default")
      (node (ref "SV1") (pin "31") (pinfunction "31_31") (pintype "passive"))
    )
    (net (code "84") (name "unconnected-(SV1-Pad32)") (class "Default")
      (node (ref "SV1") (pin "32") (pinfunction "32_32") (pintype "passive"))
    )
    (net (code "85") (name "unconnected-(SV1-Pad33)") (class "Default")
      (node (ref "SV1") (pin "33") (pinfunction "33_33") (pintype "passive"))
    )
    (net (code "86") (name "unconnected-(SV1-Pad35)") (class "Default")
      (node (ref "SV1") (pin "35") (pinfunction "35_35") (pintype "passive"))
    )
    (net (code "87") (name "unconnected-(SV1-Pad36)") (class "Default")
      (node (ref "SV1") (pin "36") (pinfunction "36_36") (pintype "passive"))
    )
    (net (code "88") (name "unconnected-(SV1-Pad37)") (class "Default")
      (node (ref "SV1") (pin "37") (pinfunction "37_37") (pintype "passive"))
    )
    (net (code "89") (name "unconnected-(SV1-Pad38)") (class "Default")
      (node (ref "SV1") (pin "38") (pinfunction "38_38") (pintype "passive"))
    )
    (net (code "90") (name "unconnected-(SV1-Pad40)") (class "Default")
      (node (ref "SV1") (pin "40") (pinfunction "40_40") (pintype "passive"))
    )
    (net (code "91") (name "unconnected-(U1A-PF14-OSC32_IN-Pad3)") (class "Default")
      (node (ref "U1") (pin "3") (pinfunction "PF14-OSC32_IN_3") (pintype "bidirectional"))
    )
    (net (code "92") (name "unconnected-(U1A-PF15-OSC32_OUT-Pad4)") (class "Default")
      (node (ref "U1") (pin "4") (pinfunction "PF15-OSC32_OUT_4") (pintype "bidirectional"))
    )
    (net (code "93") (name "unconnected-(U1B-PA11-Pad32)") (class "Default")
      (node (ref "U1") (pin "32") (pinfunction "PA11_32") (pintype "bidirectional"))
    )
    (net (code "94") (name "unconnected-(U1B-PA12-Pad33)") (class "Default")
      (node (ref "U1") (pin "33") (pinfunction "PA12_33") (pintype "bidirectional"))
    )
    (net (code "95") (name "unconnected-(U1B-PC13-Pad2)") (class "Default")
      (node (ref "U1") (pin "2") (pinfunction "PC13_2") (pintype "bidirectional"))
    )
    (net (code "96") (name "unconnected-(U1C-PB2-Pad20)") (class "Default")
      (node (ref "U1") (pin "20") (pinfunction "PB2_20") (pintype "bidirectional"))
    )
    (net (code "97") (name "unconnected-(U3-A8-Pad10)") (class "Default")
      (node (ref "U3") (pin "10") (pinfunction "A8_10") (pintype "output"))
    )
    (net (code "98") (name "unconnected-(U3-B8-Pad14)") (class "Default")
      (node (ref "U3") (pin "14") (pinfunction "B8_14") (pintype "output"))
    )
  )
)
